# OSO-MISC-21-016_Power_Test.net
KiCad netlist of a schematic drawn in EAGLE
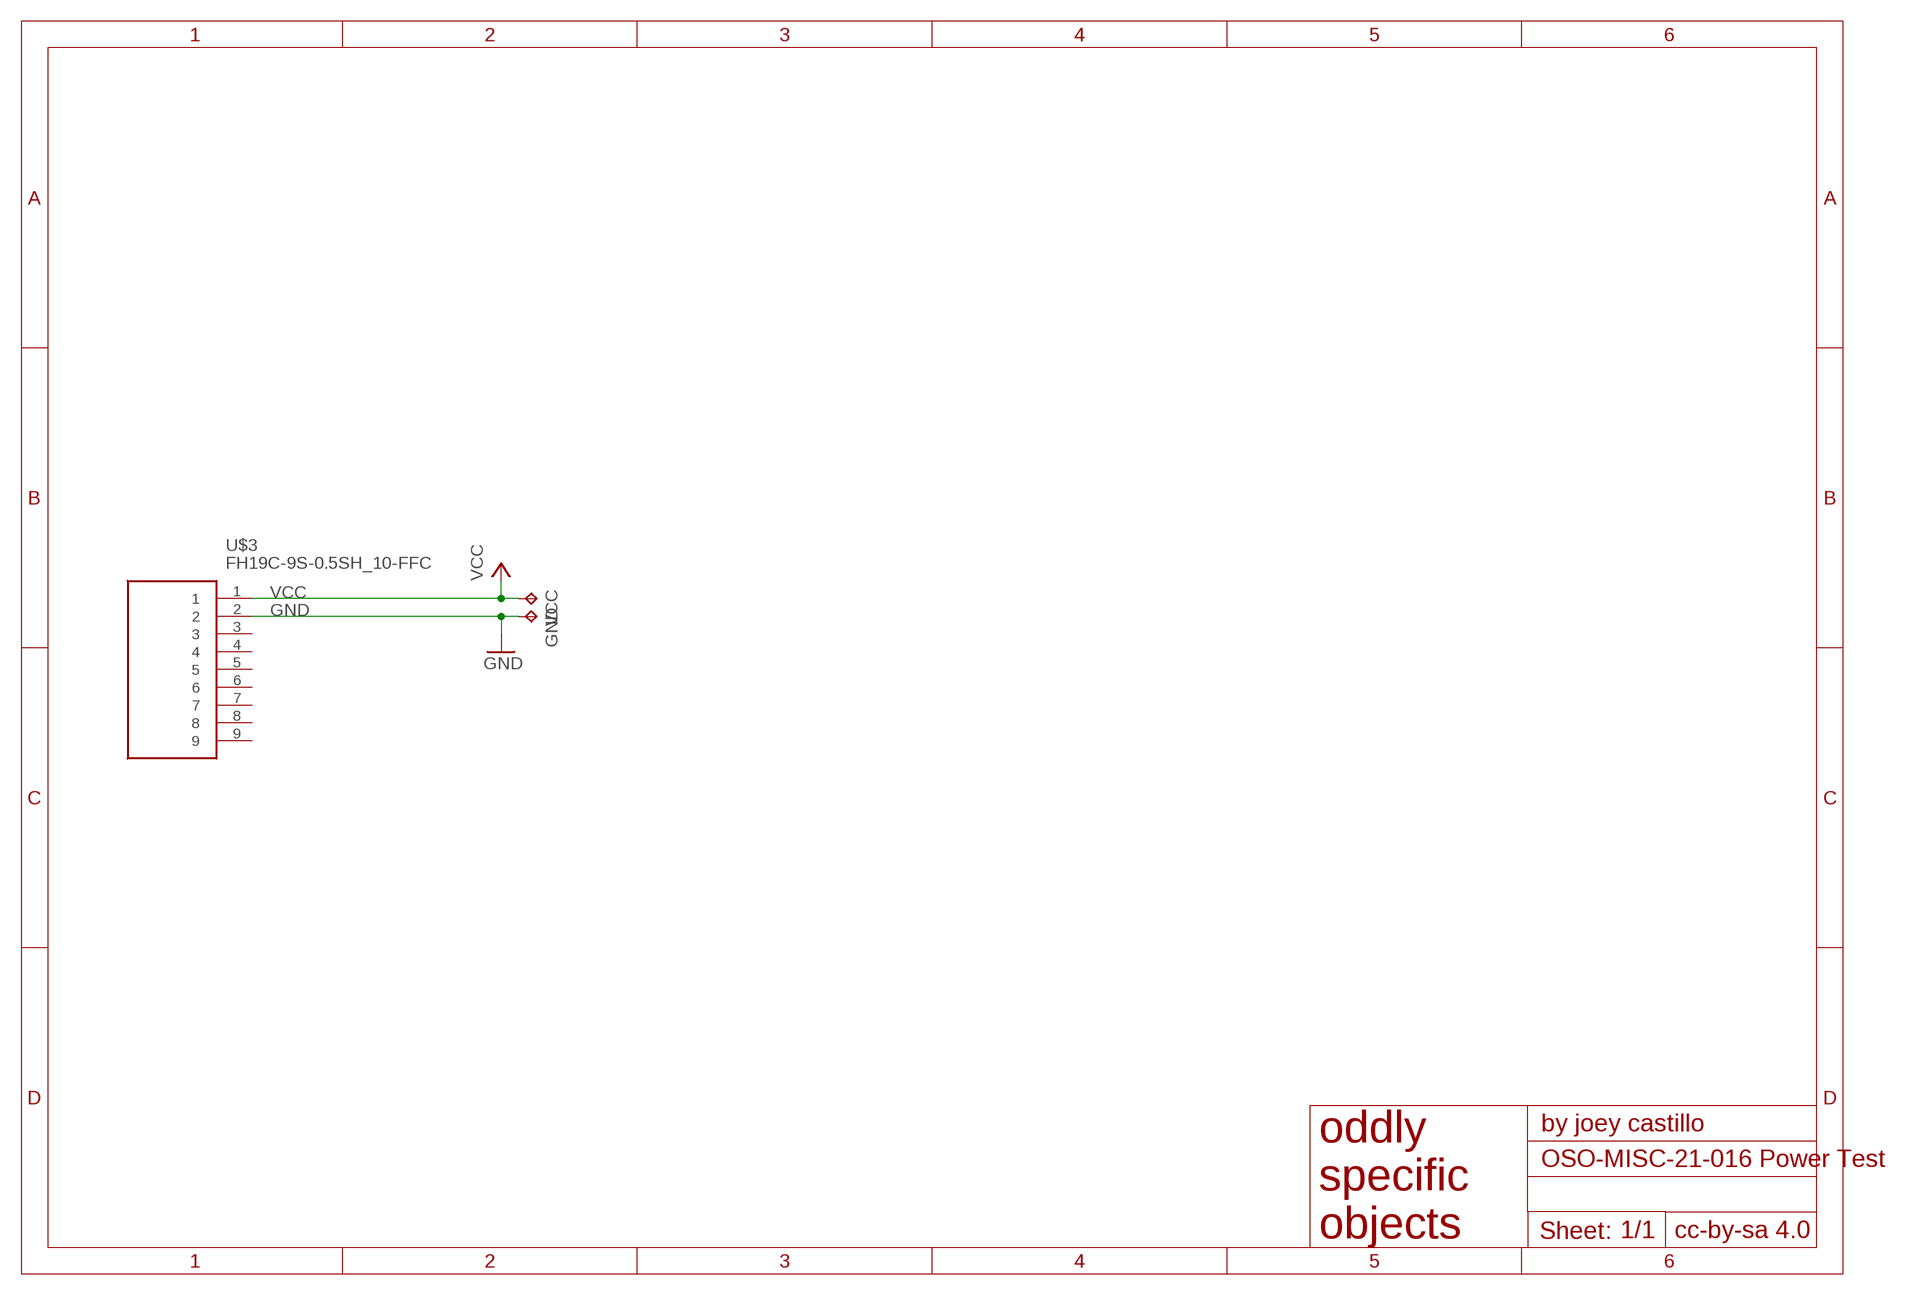
[diagram p0: schematic, sheet 1]

(export (version "E")
  (design (tool "Eeschema 10.0.6"))
  (components
    (comp (ref "GND")
      (value "TPB2,54")
      (footprint "eagle-import:B2,54")
      (libsource (lib "eagle-import") (part "TPB2,54"))
    )
    (comp (ref "U$3")
      (value "FH19C-9S-0.5SH_10-FFC")
      (footprint "eagle-import:FH19C9S05SH10-FFC")
      (libsource (lib "eagle-import") (part "FH19C-9S-0.5SH_10-FFC"))
    )
    (comp (ref "VCC")
      (value "TPB2,54")
      (footprint "eagle-import:B2,54")
      (libsource (lib "eagle-import") (part "TPB2,54"))
    )
  )
  (nets
    (net (code "1") (name "GND") (class "Default")
      (node (ref "GND") (pin "TP") (pinfunction "TP_TP") (pintype "input"))
      (node (ref "U$3") (pin "2") (pinfunction "2_2") (pintype "bidirectional"))
    )
    (net (code "2") (name "VCC") (class "Default")
      (node (ref "U$3") (pin "1") (pinfunction "1_1") (pintype "bidirectional"))
      (node (ref "VCC") (pin "TP") (pinfunction "TP_TP") (pintype "input"))
    )
    (net (code "3") (name "unconnected-(U$3-Pad3)") (class "Default")
      (node (ref "U$3") (pin "3") (pinfunction "3_3") (pintype "bidirectional"))
    )
    (net (code "4") (name "unconnected-(U$3-Pad4)") (class "Default")
      (node (ref "U$3") (pin "4") (pinfunction "4_4") (pintype "bidirectional"))
    )
    (net (code "5") (name "unconnected-(U$3-Pad5)") (class "Default")
      (node (ref "U$3") (pin "5") (pinfunction "5_5") (pintype "bidirectional"))
    )
    (net (code "6") (name "unconnected-(U$3-Pad6)") (class "Default")
      (node (ref "U$3") (pin "6") (pinfunction "6_6") (pintype "bidirectional"))
    )
    (net (code "7") (name "unconnected-(U$3-Pad7)") (class "Default")
      (node (ref "U$3") (pin "7") (pinfunction "7_7") (pintype "bidirectional"))
    )
    (net (code "8") (name "unconnected-(U$3-Pad8)") (class "Default")
      (node (ref "U$3") (pin "8") (pinfunction "8_8") (pintype "bidirectional"))
    )
    (net (code "9") (name "unconnected-(U$3-Pad9)") (class "Default")
      (node (ref "U$3") (pin "9") (pinfunction "9_9") (pintype "bidirectional"))
    )
  )
)
